# PowerSupplyAndUSB.net
KiCad netlist of a schematic drawn in Altium Designer
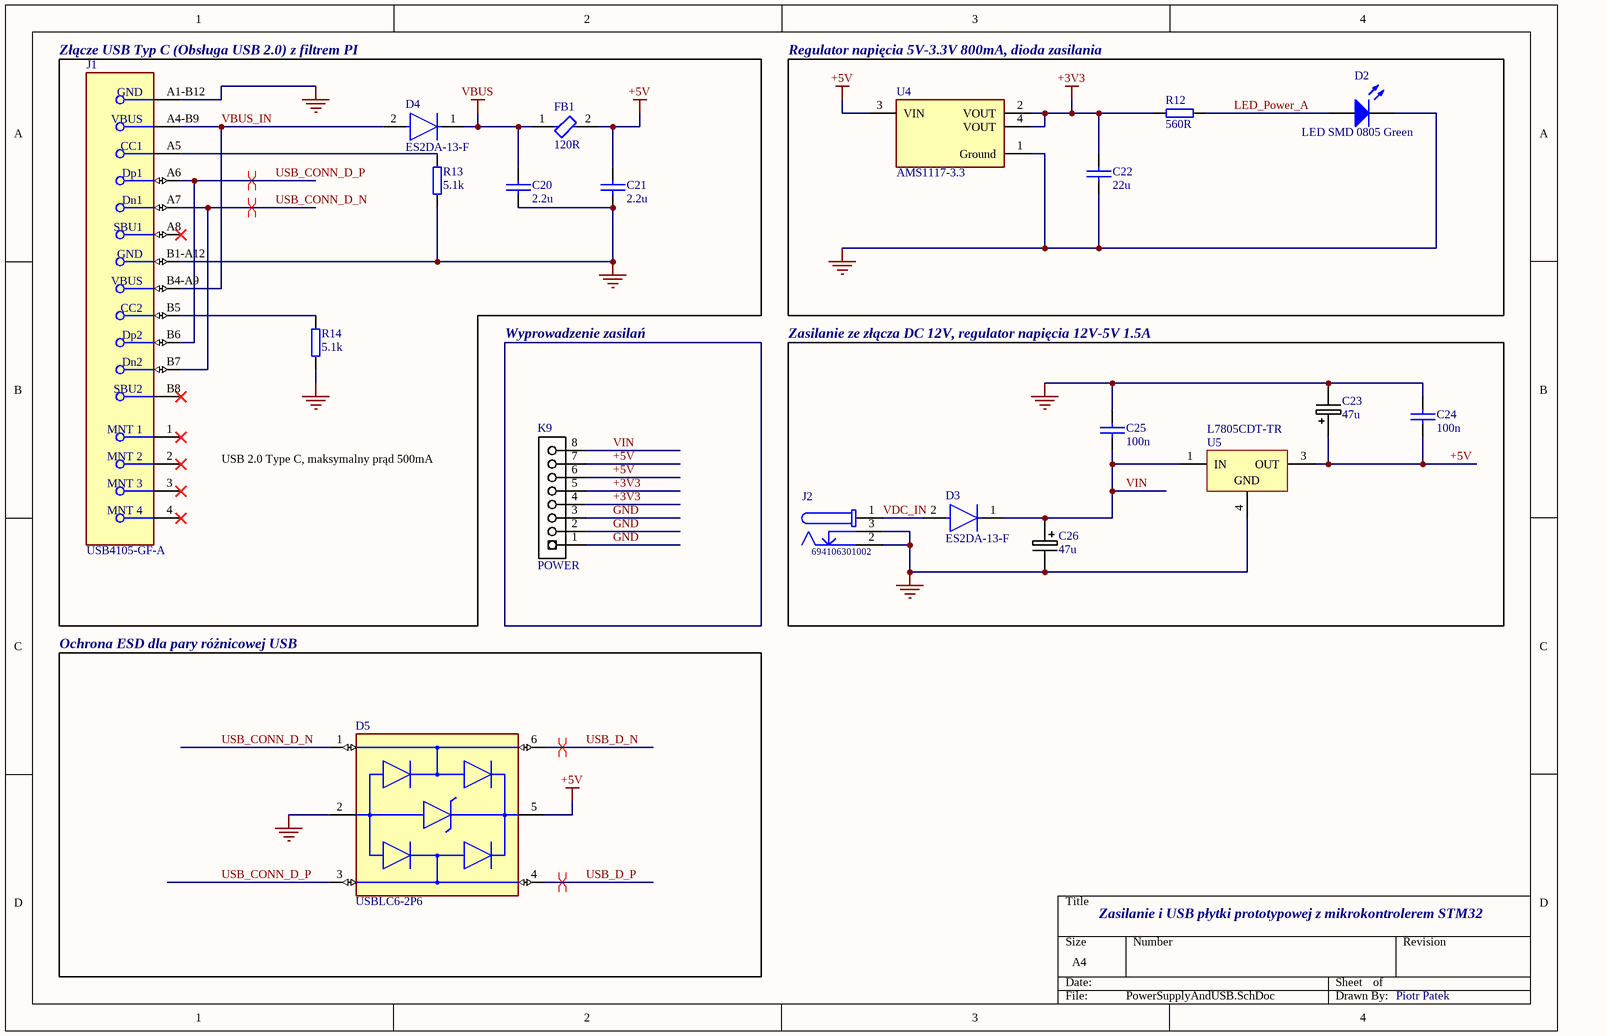
[diagram p0: PowerSupplyAndUSB.SchDoc]

(export (version "E")
  (design (tool "Eeschema 10.0.6"))
  (components
    (comp (ref "C20") (value "2.2u") (footprint "0805") (libsource (lib "Slawek_new") (part "Kondensator")))
    (comp (ref "C21") (value "2.2u") (footprint "0805") (libsource (lib "Slawek_new") (part "Kondensator")))
    (comp (ref "C22") (value "22u") (footprint "0805") (libsource (lib "Slawek_new") (part "Kondensator")))
    (comp (ref "C23")
      (value "47u")
      (footprint "PANACAP-C")
      (description "GENERIC CAPACITOR POLARISED")
      (libsource (lib "vh_altium_library") (part "C+47U-6V3"))
    )
    (comp (ref "C24") (value "100n") (footprint "0805") (libsource (lib "Slawek_new") (part "Kondensator")))
    (comp (ref "C25") (value "100n") (footprint "0805") (libsource (lib "Slawek_new") (part "Kondensator")))
    (comp (ref "C26")
      (value "47u")
      (footprint "PANACAP-C")
      (description "GENERIC CAPACITOR POLARISED")
      (libsource (lib "vh_altium_library") (part "C+47U-6V3"))
    )
    (comp (ref "D2")
      (value "LED SMD 0805 Green")
      (footprint "0805_PAD")
      (description "WURTH ELEKTRONIK - 150080GS75000 - LED, Green, SMD, 0805, 30 mA, 3.2 V, 520 nm")
      (fields
        (field (name "MANUFACTURER") "Wurth Electronics")
        (field (name "MANUFACTURER PART NUMBER") "150080GS75000")
      )
      (libsource (lib "BibliotekaPiotrek") (part "LED SMD 0805 Green"))
    )
    (comp (ref "D3")
      (value "ES2DA-13-F")
      (footprint "FP-SMA-MFG")
      (description "DIODE GEN PURP 200V 2A SMA")
      (fields
        (field (name "MANUFACTURER") "Diodes Inc.")
        (field (name "OCTOPART") "https://octopart.com/es2da-13-f-diodes+inc.-328903")
      )
      (libsource (lib "Altium Content Vault") (part "d7152d700b627762746794eb795d46e"))
    )
    (comp (ref "D4")
      (value "ES2DA-13-F")
      (footprint "FP-SMA-MFG")
      (description "DIODE GEN PURP 200V 2A SMA")
      (fields
        (field (name "MANUFACTURER") "Diodes Inc.")
        (field (name "OCTOPART") "https://octopart.com/es2da-13-f-diodes+inc.-328903")
      )
      (libsource (lib "Altium Content Vault") (part "d7152d700b627762746794eb795d46e"))
    )
    (comp (ref "D5")
      (value "USBLC6-2P6")
      (footprint "FP-SOT-666-MFG")
      (description "TVS DIODE 5.25V 17V SOT666")
      (libsource (lib "Altium Content Vault") (part "c871e55f7e3243d341edbd671b98d92"))
    )
    (comp (ref "FB1")
      (value "120R")
      (footprint "FP-BLM18-0_15-t0_8-MFG")
      (description "Chip Ferrite Bead, 0603, 120Ω @ 100MHz, 0.18Ω, 25%, 800mA")
      (fields (field (name "TOLERANCE") "25%"))
      (libsource (lib "Altium Content Vault") (part "5f30dd21d616792df468990f7003faa"))
    )
    (comp (ref "J1")
      (value "USB4105-GF-A")
      (footprint "FP-USB4105-GF-A-MFG")
      (description "CONN RCPT USB2.0 TYPEC 5A")
      (fields
        (field (name "MANUFACTURER") "GCT")
        (field (name "OCTOPART") "https://octopart.com/usb4105-gf-a-gct-106627878")
      )
      (libsource (lib "Altium Content Vault") (part "e7c17a616881a82b79941196b4bec10"))
    )
    (comp (ref "J2")
      (value "694106301002")
      (footprint "694106301002")
      (description "DC Power Jack Connector WR-DC, Male, Right Angled, THT, 5 A, 24 V")
      (fields (field (name "MANUFACTURER") "Wurth Elektronik") (field (name "PUBLISHER") "WurthElektronik"))
      (libsource (lib "Altium Content Vault") (part "WE-JACK-2CD3-RN"))
    )
    (comp (ref "K9")
      (value "POWER")
      (footprint "HEADER-1X8")
      (libsource (lib "vh_altium_library") (part "HEADER-1X8"))
    )
    (comp (ref "R12") (value "560R") (footprint "0805") (libsource (lib "Slawek_new") (part "Rezystor")))
    (comp (ref "R13") (value "5.1k") (footprint "0805") (libsource (lib "Slawek_new") (part "Rezystor")))
    (comp (ref "R14") (value "5.1k") (footprint "0805") (libsource (lib "Slawek_new") (part "Rezystor")))
    (comp (ref "U4")
      (value "AMS1117-3.3")
      (footprint "FP-AMS1117-IPC_C")
      (description "LDO Voltage Regulators 1A, 3.3V")
      (fields
        (field (name "OCTOPART") "https://octopart.com/ams1117-3.3-advanced+monolithic+systems-25899300")
        (field (name "MANUFACTURER") "Advanced Monolithic Systems")
      )
      (libsource (lib "Altium Content Vault") (part "8bdbb5f8e77002000e30dd2845d0354"))
    )
    (comp (ref "U5")
      (value "L7805CDT-TR")
      (footprint "TO-252_N")
      (description "Positive Voltage Regulator, 3-Pin DPAK, Tape and Reel")
      (libsource (lib "Altium Content Vault") (part "PM-REG-L4940-SOT3"))
    )
  )
  (nets
    (net (code "1") (name "+3V3") (class "Default")
      (node (ref "C22") (pin "2") (pinfunction "2_2") (pintype "passive"))
      (node (ref "K9") (pin "4") (pintype "passive"))
      (node (ref "K9") (pin "5") (pintype "passive"))
      (node (ref "R12") (pin "2") (pintype "passive"))
      (node (ref "U4") (pin "2") (pinfunction "VOUT_2") (pintype "passive"))
      (node (ref "U4") (pin "4") (pinfunction "VOUT_4") (pintype "passive"))
    )
    (net (code "2") (name "+5V") (class "Default")
      (node (ref "C21") (pin "2") (pinfunction "2_2") (pintype "passive"))
      (node (ref "C23") (pin "+") (pinfunction "+_+") (pintype "passive"))
      (node (ref "C24") (pin "1") (pinfunction "1_1") (pintype "passive"))
      (node (ref "D5") (pin "5") (pinfunction "VBUS_5") (pintype "power_in"))
      (node (ref "FB1") (pin "2") (pinfunction "2_2") (pintype "passive"))
      (node (ref "K9") (pin "6") (pintype "passive"))
      (node (ref "K9") (pin "7") (pintype "passive"))
      (node (ref "U4") (pin "3") (pinfunction "VIN_3") (pintype "power_in"))
      (node (ref "U5") (pin "3") (pinfunction "OUT_3") (pintype "power_in"))
    )
    (net (code "3") (name "/LED_Power_A") (class "Default")
      (node (ref "D2") (pin "2") (pinfunction "A_2") (pintype "passive"))
      (node (ref "R12") (pin "1") (pintype "passive"))
    )
    (net (code "4") (name "/USB_CONN_D_N") (class "Default")
      (node (ref "D5") (pin "1") (pinfunction "I/O1_1") (pintype "bidirectional"))
      (node (ref "J1") (pin "A7") (pinfunction "Dn1_A7") (pintype "bidirectional"))
      (node (ref "J1") (pin "B7") (pinfunction "Dn2_B7") (pintype "bidirectional"))
    )
    (net (code "5") (name "/USB_CONN_D_P") (class "Default")
      (node (ref "D5") (pin "3") (pinfunction "I/O2_3") (pintype "bidirectional"))
      (node (ref "J1") (pin "A6") (pinfunction "Dp1_A6") (pintype "bidirectional"))
      (node (ref "J1") (pin "B6") (pinfunction "Dp2_B6") (pintype "bidirectional"))
    )
    (net (code "6") (name "/USB_D_N") (class "Default")
      (node (ref "D5") (pin "6") (pinfunction "I/O1_6") (pintype "bidirectional"))
    )
    (net (code "7") (name "/USB_D_P") (class "Default")
      (node (ref "D5") (pin "4") (pinfunction "I/O2_4") (pintype "bidirectional"))
    )
    (net (code "8") (name "/VBUS_IN") (class "Default")
      (node (ref "D4") (pin "2") (pinfunction "A_2") (pintype "passive"))
      (node (ref "J1") (pin "A4-B9") (pinfunction "VBUS_A4-B9") (pintype "power_in"))
      (node (ref "J1") (pin "B4-A9") (pinfunction "VBUS_B4-A9") (pintype "bidirectional"))
    )
    (net (code "9") (name "/VDC_IN") (class "Default")
      (node (ref "D3") (pin "2") (pinfunction "A_2") (pintype "passive"))
      (node (ref "J2") (pin "1") (pinfunction "1_1") (pintype "passive"))
    )
    (net (code "10") (name "/VIN") (class "Default")
      (node (ref "C25") (pin "1") (pinfunction "1_1") (pintype "passive"))
      (node (ref "C26") (pin "+") (pinfunction "+_+") (pintype "passive"))
      (node (ref "D3") (pin "1") (pinfunction "C_1") (pintype "passive"))
      (node (ref "K9") (pin "8") (pintype "passive"))
      (node (ref "U5") (pin "1") (pinfunction "IN_1") (pintype "power_in"))
    )
    (net (code "11") (name "GND") (class "Default")
      (node (ref "C20") (pin "1") (pinfunction "1_1") (pintype "passive"))
      (node (ref "C21") (pin "1") (pinfunction "1_1") (pintype "passive"))
      (node (ref "C22") (pin "1") (pinfunction "1_1") (pintype "passive"))
      (node (ref "C23") (pin "-") (pinfunction "-_-") (pintype "passive"))
      (node (ref "C24") (pin "2") (pinfunction "2_2") (pintype "passive"))
      (node (ref "C25") (pin "2") (pinfunction "2_2") (pintype "passive"))
      (node (ref "C26") (pin "-") (pinfunction "-_-") (pintype "passive"))
      (node (ref "D2") (pin "1") (pinfunction "K_1") (pintype "passive"))
      (node (ref "D5") (pin "2") (pinfunction "GND_2") (pintype "power_in"))
      (node (ref "J1") (pin "A1-B12") (pinfunction "GND_A1-B12") (pintype "power_in"))
      (node (ref "J1") (pin "B1-A12") (pinfunction "GND_B1-A12") (pintype "bidirectional"))
      (node (ref "J2") (pin "2") (pinfunction "2_2") (pintype "passive"))
      (node (ref "J2") (pin "3") (pinfunction "3_3") (pintype "passive"))
      (node (ref "K9") (pin "1") (pintype "passive"))
      (node (ref "K9") (pin "2") (pintype "passive"))
      (node (ref "K9") (pin "3") (pintype "passive"))
      (node (ref "R13") (pin "1") (pintype "passive"))
      (node (ref "R14") (pin "1") (pintype "passive"))
      (node (ref "U4") (pin "1") (pinfunction "Ground_1") (pintype "power_in"))
      (node (ref "U5") (pin "4") (pinfunction "GND_4") (pintype "power_in"))
    )
    (net (code "12") (name "Net-(J1-CC1)") (class "Default")
      (node (ref "J1") (pin "A5") (pinfunction "CC1_A5") (pintype "power_in"))
      (node (ref "R13") (pin "2") (pintype "passive"))
    )
    (net (code "13") (name "Net-(J1-CC2)") (class "Default")
      (node (ref "J1") (pin "B5") (pinfunction "CC2_B5") (pintype "bidirectional"))
      (node (ref "R14") (pin "2") (pintype "passive"))
    )
    (net (code "14") (name "VBUS") (class "Default")
      (node (ref "C20") (pin "2") (pinfunction "2_2") (pintype "passive"))
      (node (ref "D4") (pin "1") (pinfunction "C_1") (pintype "passive"))
      (node (ref "FB1") (pin "1") (pinfunction "1_1") (pintype "passive"))
    )
    (net (code "15") (name "unconnected-(J1-MNT_1-Pad1)") (class "Default")
      (node (ref "J1") (pin "1") (pinfunction "MNT_1_1") (pintype "power_in+no_connect"))
    )
    (net (code "16") (name "unconnected-(J1-MNT_2-Pad2)") (class "Default")
      (node (ref "J1") (pin "2") (pinfunction "MNT_2_2") (pintype "power_in+no_connect"))
    )
    (net (code "17") (name "unconnected-(J1-MNT_3-Pad3)") (class "Default")
      (node (ref "J1") (pin "3") (pinfunction "MNT_3_3") (pintype "power_in+no_connect"))
    )
    (net (code "18") (name "unconnected-(J1-MNT_4-Pad4)") (class "Default")
      (node (ref "J1") (pin "4") (pinfunction "MNT_4_4") (pintype "power_in+no_connect"))
    )
    (net (code "19") (name "unconnected-(J1-SBU1-PadA8)") (class "Default")
      (node (ref "J1") (pin "A8") (pinfunction "SBU1_A8") (pintype "bidirectional+no_connect"))
    )
    (net (code "20") (name "unconnected-(J1-SBU2-PadB8)") (class "Default")
      (node (ref "J1") (pin "B8") (pinfunction "SBU2_B8") (pintype "power_in+no_connect"))
    )
  )
)
